# 00A-120.net
KiCad netlist of a schematic drawn in EAGLE
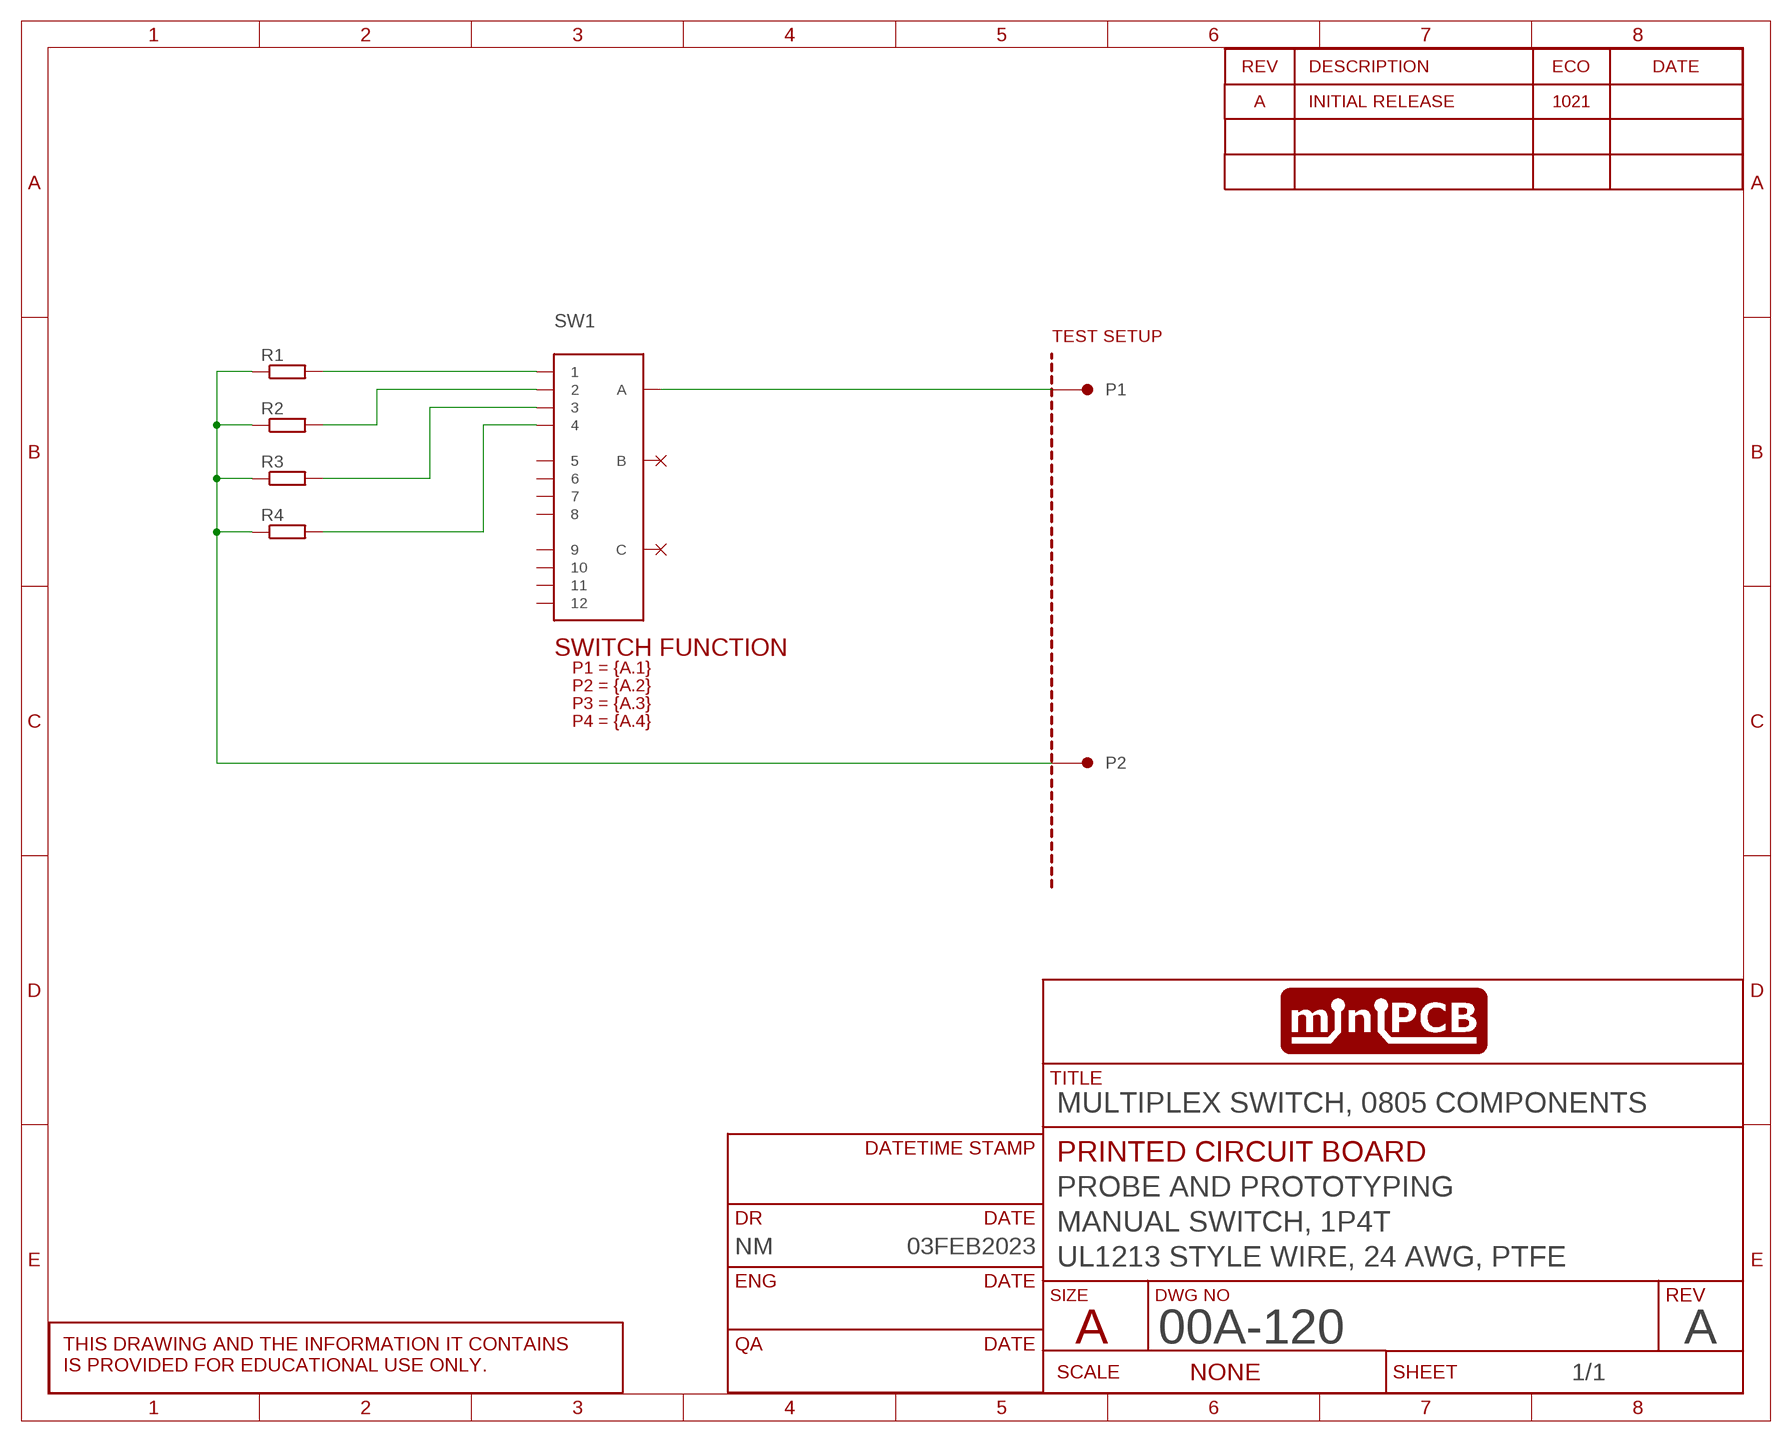
[diagram p0: schematic, sheet 1]

(export (version "E")
  (design (tool "Eeschema 10.0.6"))
  (components
    (comp (ref "P1")
      (value "PINS_124AWG-NOTEXT")
      (footprint "eagle-import:PINS_1_1MM-NOTEXT")
      (libsource (lib "eagle-import") (part "PINS_124AWG-NOTEXT"))
    )
    (comp (ref "P2")
      (value "PINS_124AWG-NOTEXT")
      (footprint "eagle-import:PINS_1_1MM-NOTEXT")
      (libsource (lib "eagle-import") (part "PINS_124AWG-NOTEXT"))
    )
    (comp (ref "PCB1")
      (value "MINIPCB_0P50X50")
      (footprint "eagle-import:MINIPCB_0P_50X50MM")
      (fields (field (name "NAME1") "TEST SETUP") (field (name "PART_NUMBER") "00A-120-A"))
      (libsource (lib "eagle-import") (part "MINIPCB_0P50X50"))
    )
    (comp (ref "R1")
      (value "RESISTORSMD")
      (footprint "eagle-import:R0805")
      (libsource (lib "eagle-import") (part "RESISTORSMD"))
    )
    (comp (ref "R2")
      (value "RESISTORSMD")
      (footprint "eagle-import:R0805")
      (libsource (lib "eagle-import") (part "RESISTORSMD"))
    )
    (comp (ref "R3")
      (value "RESISTORSMD")
      (footprint "eagle-import:R0805")
      (libsource (lib "eagle-import") (part "RESISTORSMD"))
    )
    (comp (ref "R4")
      (value "RESISTORSMD")
      (footprint "eagle-import:R0805")
      (libsource (lib "eagle-import") (part "RESISTORSMD"))
    )
    (comp (ref "SW1")
      (value "SWITCH-ROTARY-3P4T")
      (footprint "eagle-import:SWITCH-ROTARY-3P4T")
      (libsource (lib "eagle-import") (part "SWITCH-ROTARY-3P4T"))
    )
  )
  (nets
    (net (code "1") (name "Net-(P1-1-Pad2)") (class "Default")
      (node (ref "P1") (pin "1") (pinfunction "1_1") (pintype "bidirectional"))
      (node (ref "P1") (pin "2") (pinfunction "1_2") (pintype "bidirectional"))
      (node (ref "SW1") (pin "A") (pinfunction "A_A") (pintype "bidirectional"))
    )
    (net (code "2") (name "Net-(P2-1-Pad2)") (class "Default")
      (node (ref "P2") (pin "1") (pinfunction "1_1") (pintype "bidirectional"))
      (node (ref "P2") (pin "2") (pinfunction "1_2") (pintype "bidirectional"))
      (node (ref "R1") (pin "1") (pinfunction "1_1") (pintype "passive"))
      (node (ref "R2") (pin "1") (pinfunction "1_1") (pintype "passive"))
      (node (ref "R3") (pin "1") (pinfunction "1_1") (pintype "passive"))
      (node (ref "R4") (pin "1") (pinfunction "1_1") (pintype "passive"))
    )
    (net (code "3") (name "Net-(R1-Pad2)") (class "Default")
      (node (ref "R1") (pin "2") (pinfunction "2_2") (pintype "passive"))
      (node (ref "SW1") (pin "1") (pinfunction "1_1") (pintype "bidirectional"))
    )
    (net (code "4") (name "Net-(R2-Pad2)") (class "Default")
      (node (ref "R2") (pin "2") (pinfunction "2_2") (pintype "passive"))
      (node (ref "SW1") (pin "2") (pinfunction "2_2") (pintype "bidirectional"))
    )
    (net (code "5") (name "Net-(R3-Pad2)") (class "Default")
      (node (ref "R3") (pin "2") (pinfunction "2_2") (pintype "passive"))
      (node (ref "SW1") (pin "3") (pinfunction "3_3") (pintype "bidirectional"))
    )
    (net (code "6") (name "Net-(R4-Pad2)") (class "Default")
      (node (ref "R4") (pin "2") (pinfunction "2_2") (pintype "passive"))
      (node (ref "SW1") (pin "4") (pinfunction "4_4") (pintype "bidirectional"))
    )
    (net (code "7") (name "unconnected-(SW1-Pad5)") (class "Default")
      (node (ref "SW1") (pin "5") (pinfunction "5_5") (pintype "bidirectional"))
    )
    (net (code "8") (name "unconnected-(SW1-Pad6)") (class "Default")
      (node (ref "SW1") (pin "6") (pinfunction "6_6") (pintype "bidirectional"))
    )
    (net (code "9") (name "unconnected-(SW1-Pad7)") (class "Default")
      (node (ref "SW1") (pin "7") (pinfunction "7_7") (pintype "bidirectional"))
    )
    (net (code "10") (name "unconnected-(SW1-Pad8)") (class "Default")
      (node (ref "SW1") (pin "8") (pinfunction "8_8") (pintype "bidirectional"))
    )
    (net (code "11") (name "unconnected-(SW1-Pad9)") (class "Default")
      (node (ref "SW1") (pin "9") (pinfunction "9_9") (pintype "bidirectional"))
    )
    (net (code "12") (name "unconnected-(SW1-Pad10)") (class "Default")
      (node (ref "SW1") (pin "10") (pinfunction "10_10") (pintype "bidirectional"))
    )
    (net (code "13") (name "unconnected-(SW1-Pad11)") (class "Default")
      (node (ref "SW1") (pin "11") (pinfunction "11_11") (pintype "bidirectional"))
    )
    (net (code "14") (name "unconnected-(SW1-Pad12)") (class "Default")
      (node (ref "SW1") (pin "12") (pinfunction "12_12") (pintype "bidirectional"))
    )
    (net (code "15") (name "unconnected-(SW1-PadB)") (class "Default")
      (node (ref "SW1") (pin "B") (pinfunction "B_B") (pintype "bidirectional"))
    )
    (net (code "16") (name "unconnected-(SW1-PadC)") (class "Default")
      (node (ref "SW1") (pin "C") (pinfunction "C_C") (pintype "bidirectional"))
    )
  )
)
